# Reid_Orthotic_v2_IO.net
KiCad netlist of a schematic drawn in Altium Designer
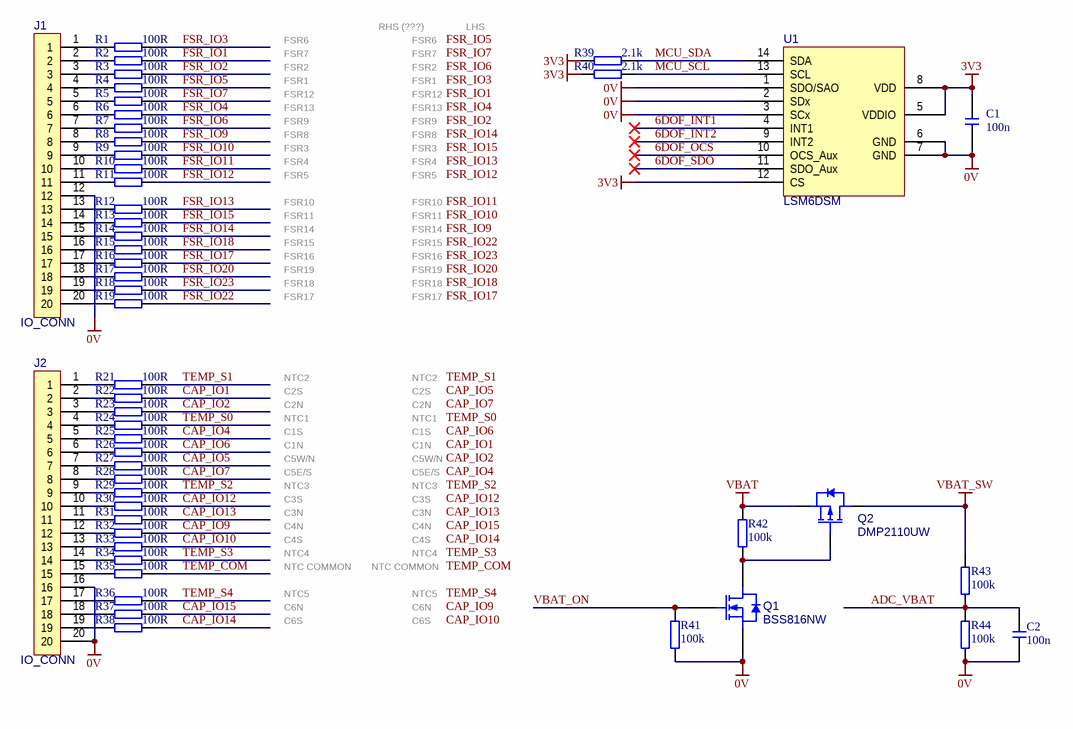
[diagram p0: Reid Orthotic v2 IO.SchDoc]

(export (version "E")
  (design (tool "Eeschema 10.0.6"))
  (components
    (comp (ref "C1")
      (value "100n")
      (footprint "0402 CAP HD")
      (libsource (lib "zoo589 PCB Library") (part "Capacitor"))
    )
    (comp (ref "C2")
      (value "100n")
      (footprint "0402 CAP HD")
      (libsource (lib "zoo589 PCB Library") (part "Capacitor"))
    )
    (comp (ref "J1")
      (value "IO_CONN")
      (footprint "IO_CONN")
      (libsource (lib "Reid Orthotic v2") (part "IO_CONN"))
    )
    (comp (ref "J2")
      (value "IO_CONN")
      (footprint "IO_CONN")
      (libsource (lib "Reid Orthotic v2") (part "IO_CONN"))
    )
    (comp (ref "Q1")
      (value "BSS816NW")
      (footprint "SOT323")
      (libsource (lib "Earthoffset Prototype v1 PCB Library") (part "MOSFET N-CH"))
    )
    (comp (ref "Q2")
      (value "DMP2110UW")
      (footprint "SOT323")
      (libsource (lib "zoo589 PCB Library") (part "MOSFET PCH"))
    )
    (comp (ref "R1")
      (value "100R")
      (footprint "0402 RES HD")
      (libsource (lib "zoo589 PCB Library") (part "Resistor"))
    )
    (comp (ref "R2")
      (value "100R")
      (footprint "0402 RES HD")
      (libsource (lib "zoo589 PCB Library") (part "Resistor"))
    )
    (comp (ref "R3")
      (value "100R")
      (footprint "0402 RES HD")
      (libsource (lib "zoo589 PCB Library") (part "Resistor"))
    )
    (comp (ref "R4")
      (value "100R")
      (footprint "0402 RES HD")
      (libsource (lib "zoo589 PCB Library") (part "Resistor"))
    )
    (comp (ref "R5")
      (value "100R")
      (footprint "0402 RES HD")
      (libsource (lib "zoo589 PCB Library") (part "Resistor"))
    )
    (comp (ref "R6")
      (value "100R")
      (footprint "0402 RES HD")
      (libsource (lib "zoo589 PCB Library") (part "Resistor"))
    )
    (comp (ref "R7")
      (value "100R")
      (footprint "0402 RES HD")
      (libsource (lib "zoo589 PCB Library") (part "Resistor"))
    )
    (comp (ref "R8")
      (value "100R")
      (footprint "0402 RES HD")
      (libsource (lib "zoo589 PCB Library") (part "Resistor"))
    )
    (comp (ref "R9")
      (value "100R")
      (footprint "0402 RES HD")
      (libsource (lib "zoo589 PCB Library") (part "Resistor"))
    )
    (comp (ref "R10")
      (value "100R")
      (footprint "0402 RES HD")
      (libsource (lib "zoo589 PCB Library") (part "Resistor"))
    )
    (comp (ref "R11")
      (value "100R")
      (footprint "0402 RES HD")
      (libsource (lib "zoo589 PCB Library") (part "Resistor"))
    )
    (comp (ref "R12")
      (value "100R")
      (footprint "0402 RES HD")
      (libsource (lib "zoo589 PCB Library") (part "Resistor"))
    )
    (comp (ref "R13")
      (value "100R")
      (footprint "0402 RES HD")
      (libsource (lib "zoo589 PCB Library") (part "Resistor"))
    )
    (comp (ref "R14")
      (value "100R")
      (footprint "0402 RES HD")
      (libsource (lib "zoo589 PCB Library") (part "Resistor"))
    )
    (comp (ref "R15")
      (value "100R")
      (footprint "0402 RES HD")
      (libsource (lib "zoo589 PCB Library") (part "Resistor"))
    )
    (comp (ref "R16")
      (value "100R")
      (footprint "0402 RES HD")
      (libsource (lib "zoo589 PCB Library") (part "Resistor"))
    )
    (comp (ref "R17")
      (value "100R")
      (footprint "0402 RES HD")
      (libsource (lib "zoo589 PCB Library") (part "Resistor"))
    )
    (comp (ref "R18")
      (value "100R")
      (footprint "0402 RES HD")
      (libsource (lib "zoo589 PCB Library") (part "Resistor"))
    )
    (comp (ref "R19")
      (value "100R")
      (footprint "0402 RES HD")
      (libsource (lib "zoo589 PCB Library") (part "Resistor"))
    )
    (comp (ref "R21")
      (value "100R")
      (footprint "0402 RES HD")
      (libsource (lib "zoo589 PCB Library") (part "Resistor"))
    )
    (comp (ref "R22")
      (value "100R")
      (footprint "0402 RES HD")
      (libsource (lib "zoo589 PCB Library") (part "Resistor"))
    )
    (comp (ref "R23")
      (value "100R")
      (footprint "0402 RES HD")
      (libsource (lib "zoo589 PCB Library") (part "Resistor"))
    )
    (comp (ref "R24")
      (value "100R")
      (footprint "0402 RES HD")
      (libsource (lib "zoo589 PCB Library") (part "Resistor"))
    )
    (comp (ref "R25")
      (value "100R")
      (footprint "0402 RES HD")
      (libsource (lib "zoo589 PCB Library") (part "Resistor"))
    )
    (comp (ref "R26")
      (value "100R")
      (footprint "0402 RES HD")
      (libsource (lib "zoo589 PCB Library") (part "Resistor"))
    )
    (comp (ref "R27")
      (value "100R")
      (footprint "0402 RES HD")
      (libsource (lib "zoo589 PCB Library") (part "Resistor"))
    )
    (comp (ref "R28")
      (value "100R")
      (footprint "0402 RES HD")
      (libsource (lib "zoo589 PCB Library") (part "Resistor"))
    )
    (comp (ref "R29")
      (value "100R")
      (footprint "0402 RES HD")
      (libsource (lib "zoo589 PCB Library") (part "Resistor"))
    )
    (comp (ref "R30")
      (value "100R")
      (footprint "0402 RES HD")
      (libsource (lib "zoo589 PCB Library") (part "Resistor"))
    )
    (comp (ref "R31")
      (value "100R")
      (footprint "0402 RES HD")
      (libsource (lib "zoo589 PCB Library") (part "Resistor"))
    )
    (comp (ref "R32")
      (value "100R")
      (footprint "0402 RES HD")
      (libsource (lib "zoo589 PCB Library") (part "Resistor"))
    )
    (comp (ref "R33")
      (value "100R")
      (footprint "0402 RES HD")
      (libsource (lib "zoo589 PCB Library") (part "Resistor"))
    )
    (comp (ref "R34")
      (value "100R")
      (footprint "0402 RES HD")
      (libsource (lib "zoo589 PCB Library") (part "Resistor"))
    )
    (comp (ref "R35")
      (value "100R")
      (footprint "0402 RES HD")
      (libsource (lib "zoo589 PCB Library") (part "Resistor"))
    )
    (comp (ref "R36")
      (value "100R")
      (footprint "0402 RES HD")
      (libsource (lib "zoo589 PCB Library") (part "Resistor"))
    )
    (comp (ref "R37")
      (value "100R")
      (footprint "0402 RES HD")
      (libsource (lib "zoo589 PCB Library") (part "Resistor"))
    )
    (comp (ref "R38")
      (value "100R")
      (footprint "0402 RES HD")
      (libsource (lib "zoo589 PCB Library") (part "Resistor"))
    )
    (comp (ref "R39")
      (value "2.1k")
      (footprint "0402 RES HD")
      (libsource (lib "zoo589 PCB Library") (part "Resistor"))
    )
    (comp (ref "R40")
      (value "2.1k")
      (footprint "0402 RES HD")
      (libsource (lib "zoo589 PCB Library") (part "Resistor"))
    )
    (comp (ref "R41")
      (value "100k")
      (footprint "0402 RES HD")
      (libsource (lib "zoo589 PCB Library") (part "Resistor"))
    )
    (comp (ref "R42")
      (value "100k")
      (footprint "0402 RES HD")
      (libsource (lib "zoo589 PCB Library") (part "Resistor"))
    )
    (comp (ref "R43")
      (value "100k")
      (footprint "0402 RES HD")
      (libsource (lib "zoo589 PCB Library") (part "Resistor"))
    )
    (comp (ref "R44")
      (value "100k")
      (footprint "0402 RES HD")
      (libsource (lib "zoo589 PCB Library") (part "Resistor"))
    )
    (comp (ref "U1")
      (value "LSM6DSM")
      (footprint "LSM6DSM")
      (libsource (lib "CarbonCircuits Part Library") (part "LSM6DSM"))
    )
  )
  (nets
    (net (code "1") (name "/6DOF_INT1") (class "Default")
      (node (ref "U1") (pin "4") (pinfunction "INT1_4") (pintype "passive+no_connect"))
    )
    (net (code "2") (name "/6DOF_INT2") (class "Default")
      (node (ref "U1") (pin "9") (pinfunction "INT2_9") (pintype "passive+no_connect"))
    )
    (net (code "3") (name "/6DOF_OCS") (class "Default")
      (node (ref "U1") (pin "10") (pinfunction "OCS_Aux_10") (pintype "passive+no_connect"))
    )
    (net (code "4") (name "/6DOF_SDO") (class "Default")
      (node (ref "U1") (pin "11") (pinfunction "SDO_Aux_11") (pintype "passive+no_connect"))
    )
    (net (code "5") (name "/ADC_VBAT") (class "Default")
      (node (ref "C2") (pin "1") (pinfunction "1_1") (pintype "passive"))
      (node (ref "R43") (pin "2") (pinfunction "2_2") (pintype "passive"))
      (node (ref "R44") (pin "1") (pinfunction "1_1") (pintype "passive"))
    )
    (net (code "6") (name "/CAP_IO1") (class "Default")
      (node (ref "R22") (pin "1") (pinfunction "1_1") (pintype "passive"))
    )
    (net (code "7") (name "/CAP_IO2") (class "Default")
      (node (ref "R23") (pin "1") (pinfunction "1_1") (pintype "passive"))
    )
    (net (code "8") (name "/CAP_IO4") (class "Default")
      (node (ref "R25") (pin "1") (pinfunction "1_1") (pintype "passive"))
    )
    (net (code "9") (name "/CAP_IO5") (class "Default")
      (node (ref "R27") (pin "1") (pinfunction "1_1") (pintype "passive"))
    )
    (net (code "10") (name "/CAP_IO6") (class "Default")
      (node (ref "R26") (pin "1") (pinfunction "1_1") (pintype "passive"))
    )
    (net (code "11") (name "/CAP_IO7") (class "Default")
      (node (ref "R28") (pin "1") (pinfunction "1_1") (pintype "passive"))
    )
    (net (code "12") (name "/CAP_IO9") (class "Default")
      (node (ref "R32") (pin "1") (pinfunction "1_1") (pintype "passive"))
    )
    (net (code "13") (name "/CAP_IO10") (class "Default")
      (node (ref "R33") (pin "1") (pinfunction "1_1") (pintype "passive"))
    )
    (net (code "14") (name "/CAP_IO12") (class "Default")
      (node (ref "R30") (pin "1") (pinfunction "1_1") (pintype "passive"))
    )
    (net (code "15") (name "/CAP_IO13") (class "Default")
      (node (ref "R31") (pin "1") (pinfunction "1_1") (pintype "passive"))
    )
    (net (code "16") (name "/CAP_IO14") (class "Default")
      (node (ref "R38") (pin "1") (pinfunction "1_1") (pintype "passive"))
    )
    (net (code "17") (name "/CAP_IO15") (class "Default")
      (node (ref "R37") (pin "1") (pinfunction "1_1") (pintype "passive"))
    )
    (net (code "18") (name "/FSR_IO1") (class "Default")
      (node (ref "R2") (pin "1") (pinfunction "1_1") (pintype "passive"))
    )
    (net (code "19") (name "/FSR_IO2") (class "Default")
      (node (ref "R3") (pin "1") (pinfunction "1_1") (pintype "passive"))
    )
    (net (code "20") (name "/FSR_IO3") (class "Default")
      (node (ref "R1") (pin "1") (pinfunction "1_1") (pintype "passive"))
    )
    (net (code "21") (name "/FSR_IO4") (class "Default")
      (node (ref "R6") (pin "1") (pinfunction "1_1") (pintype "passive"))
    )
    (net (code "22") (name "/FSR_IO5") (class "Default")
      (node (ref "R4") (pin "1") (pinfunction "1_1") (pintype "passive"))
    )
    (net (code "23") (name "/FSR_IO6") (class "Default")
      (node (ref "R7") (pin "1") (pinfunction "1_1") (pintype "passive"))
    )
    (net (code "24") (name "/FSR_IO7") (class "Default")
      (node (ref "R5") (pin "1") (pinfunction "1_1") (pintype "passive"))
    )
    (net (code "25") (name "/FSR_IO9") (class "Default")
      (node (ref "R8") (pin "1") (pinfunction "1_1") (pintype "passive"))
    )
    (net (code "26") (name "/FSR_IO10") (class "Default")
      (node (ref "R9") (pin "1") (pinfunction "1_1") (pintype "passive"))
    )
    (net (code "27") (name "/FSR_IO11") (class "Default")
      (node (ref "R10") (pin "1") (pinfunction "1_1") (pintype "passive"))
    )
    (net (code "28") (name "/FSR_IO12") (class "Default")
      (node (ref "R11") (pin "1") (pinfunction "1_1") (pintype "passive"))
    )
    (net (code "29") (name "/FSR_IO13") (class "Default")
      (node (ref "R12") (pin "1") (pinfunction "1_1") (pintype "passive"))
    )
    (net (code "30") (name "/FSR_IO14") (class "Default")
      (node (ref "R14") (pin "1") (pinfunction "1_1") (pintype "passive"))
    )
    (net (code "31") (name "/FSR_IO15") (class "Default")
      (node (ref "R13") (pin "1") (pinfunction "1_1") (pintype "passive"))
    )
    (net (code "32") (name "/FSR_IO17") (class "Default")
      (node (ref "R16") (pin "1") (pinfunction "1_1") (pintype "passive"))
    )
    (net (code "33") (name "/FSR_IO18") (class "Default")
      (node (ref "R15") (pin "1") (pinfunction "1_1") (pintype "passive"))
    )
    (net (code "34") (name "/FSR_IO20") (class "Default")
      (node (ref "R17") (pin "1") (pinfunction "1_1") (pintype "passive"))
    )
    (net (code "35") (name "/FSR_IO22") (class "Default")
      (node (ref "R19") (pin "1") (pinfunction "1_1") (pintype "passive"))
    )
    (net (code "36") (name "/FSR_IO23") (class "Default")
      (node (ref "R18") (pin "1") (pinfunction "1_1") (pintype "passive"))
    )
    (net (code "37") (name "/MCU_SCL") (class "Default")
      (node (ref "R40") (pin "1") (pinfunction "1_1") (pintype "passive"))
      (node (ref "U1") (pin "13") (pinfunction "SCL_13") (pintype "passive"))
    )
    (net (code "38") (name "/MCU_SDA") (class "Default")
      (node (ref "R39") (pin "1") (pinfunction "1_1") (pintype "passive"))
      (node (ref "U1") (pin "14") (pinfunction "SDA_14") (pintype "passive"))
    )
    (net (code "39") (name "/TEMP_COM") (class "Default")
      (node (ref "R35") (pin "1") (pinfunction "1_1") (pintype "passive"))
    )
    (net (code "40") (name "/TEMP_S0") (class "Default")
      (node (ref "R24") (pin "1") (pinfunction "1_1") (pintype "passive"))
    )
    (net (code "41") (name "/TEMP_S1") (class "Default")
      (node (ref "R21") (pin "1") (pinfunction "1_1") (pintype "passive"))
    )
    (net (code "42") (name "/TEMP_S2") (class "Default")
      (node (ref "R29") (pin "1") (pinfunction "1_1") (pintype "passive"))
    )
    (net (code "43") (name "/TEMP_S3") (class "Default")
      (node (ref "R34") (pin "1") (pinfunction "1_1") (pintype "passive"))
    )
    (net (code "44") (name "/TEMP_S4") (class "Default")
      (node (ref "R36") (pin "1") (pinfunction "1_1") (pintype "passive"))
    )
    (net (code "45") (name "/VBAT_ON") (class "Default")
      (node (ref "Q1") (pin "1") (pinfunction "G_1") (pintype "passive"))
      (node (ref "R41") (pin "1") (pinfunction "1_1") (pintype "passive"))
    )
    (net (code "46") (name "0V") (class "Default")
      (node (ref "C1") (pin "1") (pinfunction "1_1") (pintype "passive"))
      (node (ref "C2") (pin "2") (pinfunction "2_2") (pintype "passive"))
      (node (ref "J1") (pin "12") (pinfunction "12_12") (pintype "passive"))
      (node (ref "J2") (pin "16") (pinfunction "16_16") (pintype "passive"))
      (node (ref "J2") (pin "20") (pinfunction "20_20") (pintype "passive"))
      (node (ref "Q1") (pin "2") (pinfunction "S_2") (pintype "passive"))
      (node (ref "R41") (pin "2") (pinfunction "2_2") (pintype "passive"))
      (node (ref "R44") (pin "2") (pinfunction "2_2") (pintype "passive"))
      (node (ref "U1") (pin "1") (pinfunction "SDO/SAO_1") (pintype "passive"))
      (node (ref "U1") (pin "2") (pinfunction "SDx_2") (pintype "passive"))
      (node (ref "U1") (pin "3") (pinfunction "SCx_3") (pintype "passive"))
      (node (ref "U1") (pin "6") (pinfunction "GND_6") (pintype "passive"))
      (node (ref "U1") (pin "7") (pinfunction "GND_7") (pintype "passive"))
    )
    (net (code "47") (name "3V3") (class "Default")
      (node (ref "C1") (pin "2") (pinfunction "2_2") (pintype "passive"))
      (node (ref "R39") (pin "2") (pinfunction "2_2") (pintype "passive"))
      (node (ref "R40") (pin "2") (pinfunction "2_2") (pintype "passive"))
      (node (ref "U1") (pin "12") (pinfunction "CS_12") (pintype "passive"))
      (node (ref "U1") (pin "5") (pinfunction "VDDIO_5") (pintype "passive"))
      (node (ref "U1") (pin "8") (pinfunction "VDD_8") (pintype "passive"))
    )
    (net (code "48") (name "Net-(J1-Pad1)") (class "Default")
      (node (ref "J1") (pin "1") (pinfunction "1_1") (pintype "passive"))
      (node (ref "R1") (pin "2") (pinfunction "2_2") (pintype "passive"))
    )
    (net (code "49") (name "Net-(J1-Pad2)") (class "Default")
      (node (ref "J1") (pin "2") (pinfunction "2_2") (pintype "passive"))
      (node (ref "R2") (pin "2") (pinfunction "2_2") (pintype "passive"))
    )
    (net (code "50") (name "Net-(J1-Pad3)") (class "Default")
      (node (ref "J1") (pin "3") (pinfunction "3_3") (pintype "passive"))
      (node (ref "R3") (pin "2") (pinfunction "2_2") (pintype "passive"))
    )
    (net (code "51") (name "Net-(J1-Pad4)") (class "Default")
      (node (ref "J1") (pin "4") (pinfunction "4_4") (pintype "passive"))
      (node (ref "R4") (pin "2") (pinfunction "2_2") (pintype "passive"))
    )
    (net (code "52") (name "Net-(J1-Pad5)") (class "Default")
      (node (ref "J1") (pin "5") (pinfunction "5_5") (pintype "passive"))
      (node (ref "R5") (pin "2") (pinfunction "2_2") (pintype "passive"))
    )
    (net (code "53") (name "Net-(J1-Pad6)") (class "Default")
      (node (ref "J1") (pin "6") (pinfunction "6_6") (pintype "passive"))
      (node (ref "R6") (pin "2") (pinfunction "2_2") (pintype "passive"))
    )
    (net (code "54") (name "Net-(J1-Pad7)") (class "Default")
      (node (ref "J1") (pin "7") (pinfunction "7_7") (pintype "passive"))
      (node (ref "R7") (pin "2") (pinfunction "2_2") (pintype "passive"))
    )
    (net (code "55") (name "Net-(J1-Pad8)") (class "Default")
      (node (ref "J1") (pin "8") (pinfunction "8_8") (pintype "passive"))
      (node (ref "R8") (pin "2") (pinfunction "2_2") (pintype "passive"))
    )
    (net (code "56") (name "Net-(J1-Pad9)") (class "Default")
      (node (ref "J1") (pin "9") (pinfunction "9_9") (pintype "passive"))
      (node (ref "R9") (pin "2") (pinfunction "2_2") (pintype "passive"))
    )
    (net (code "57") (name "Net-(J1-Pad10)") (class "Default")
      (node (ref "J1") (pin "10") (pinfunction "10_10") (pintype "passive"))
      (node (ref "R10") (pin "2") (pinfunction "2_2") (pintype "passive"))
    )
    (net (code "58") (name "Net-(J1-Pad11)") (class "Default")
      (node (ref "J1") (pin "11") (pinfunction "11_11") (pintype "passive"))
      (node (ref "R11") (pin "2") (pinfunction "2_2") (pintype "passive"))
    )
    (net (code "59") (name "Net-(J1-Pad13)") (class "Default")
      (node (ref "J1") (pin "13") (pinfunction "13_13") (pintype "passive"))
      (node (ref "R12") (pin "2") (pinfunction "2_2") (pintype "passive"))
    )
    (net (code "60") (name "Net-(J1-Pad14)") (class "Default")
      (node (ref "J1") (pin "14") (pinfunction "14_14") (pintype "passive"))
      (node (ref "R13") (pin "2") (pinfunction "2_2") (pintype "passive"))
    )
    (net (code "61") (name "Net-(J1-Pad15)") (class "Default")
      (node (ref "J1") (pin "15") (pinfunction "15_15") (pintype "passive"))
      (node (ref "R14") (pin "2") (pinfunction "2_2") (pintype "passive"))
    )
    (net (code "62") (name "Net-(J1-Pad16)") (class "Default")
      (node (ref "J1") (pin "16") (pinfunction "16_16") (pintype "passive"))
      (node (ref "R15") (pin "2") (pinfunction "2_2") (pintype "passive"))
    )
    (net (code "63") (name "Net-(J1-Pad17)") (class "Default")
      (node (ref "J1") (pin "17") (pinfunction "17_17") (pintype "passive"))
      (node (ref "R16") (pin "2") (pinfunction "2_2") (pintype "passive"))
    )
    (net (code "64") (name "Net-(J1-Pad18)") (class "Default")
      (node (ref "J1") (pin "18") (pinfunction "18_18") (pintype "passive"))
      (node (ref "R17") (pin "2") (pinfunction "2_2") (pintype "passive"))
    )
    (net (code "65") (name "Net-(J1-Pad19)") (class "Default")
      (node (ref "J1") (pin "19") (pinfunction "19_19") (pintype "passive"))
      (node (ref "R18") (pin "2") (pinfunction "2_2") (pintype "passive"))
    )
    (net (code "66") (name "Net-(J1-Pad20)") (class "Default")
      (node (ref "J1") (pin "20") (pinfunction "20_20") (pintype "passive"))
      (node (ref "R19") (pin "2") (pinfunction "2_2") (pintype "passive"))
    )
    (net (code "67") (name "Net-(J2-Pad1)") (class "Default")
      (node (ref "J2") (pin "1") (pinfunction "1_1") (pintype "passive"))
      (node (ref "R21") (pin "2") (pinfunction "2_2") (pintype "passive"))
    )
    (net (code "68") (name "Net-(J2-Pad2)") (class "Default")
      (node (ref "J2") (pin "2") (pinfunction "2_2") (pintype "passive"))
      (node (ref "R22") (pin "2") (pinfunction "2_2") (pintype "passive"))
    )
    (net (code "69") (name "Net-(J2-Pad3)") (class "Default")
      (node (ref "J2") (pin "3") (pinfunction "3_3") (pintype "passive"))
      (node (ref "R23") (pin "2") (pinfunction "2_2") (pintype "passive"))
    )
    (net (code "70") (name "Net-(J2-Pad4)") (class "Default")
      (node (ref "J2") (pin "4") (pinfunction "4_4") (pintype "passive"))
      (node (ref "R24") (pin "2") (pinfunction "2_2") (pintype "passive"))
    )
    (net (code "71") (name "Net-(J2-Pad5)") (class "Default")
      (node (ref "J2") (pin "5") (pinfunction "5_5") (pintype "passive"))
      (node (ref "R25") (pin "2") (pinfunction "2_2") (pintype "passive"))
    )
    (net (code "72") (name "Net-(J2-Pad6)") (class "Default")
      (node (ref "J2") (pin "6") (pinfunction "6_6") (pintype "passive"))
      (node (ref "R26") (pin "2") (pinfunction "2_2") (pintype "passive"))
    )
    (net (code "73") (name "Net-(J2-Pad7)") (class "Default")
      (node (ref "J2") (pin "7") (pinfunction "7_7") (pintype "passive"))
      (node (ref "R27") (pin "2") (pinfunction "2_2") (pintype "passive"))
    )
    (net (code "74") (name "Net-(J2-Pad8)") (class "Default")
      (node (ref "J2") (pin "8") (pinfunction "8_8") (pintype "passive"))
      (node (ref "R28") (pin "2") (pinfunction "2_2") (pintype "passive"))
    )
    (net (code "75") (name "Net-(J2-Pad9)") (class "Default")
      (node (ref "J2") (pin "9") (pinfunction "9_9") (pintype "passive"))
      (node (ref "R29") (pin "2") (pinfunction "2_2") (pintype "passive"))
    )
    (net (code "76") (name "Net-(J2-Pad10)") (class "Default")
      (node (ref "J2") (pin "10") (pinfunction "10_10") (pintype "passive"))
      (node (ref "R30") (pin "2") (pinfunction "2_2") (pintype "passive"))
    )
    (net (code "77") (name "Net-(J2-Pad11)") (class "Default")
      (node (ref "J2") (pin "11") (pinfunction "11_11") (pintype "passive"))
      (node (ref "R31") (pin "2") (pinfunction "2_2") (pintype "passive"))
    )
    (net (code "78") (name "Net-(J2-Pad12)") (class "Default")
      (node (ref "J2") (pin "12") (pinfunction "12_12") (pintype "passive"))
      (node (ref "R32") (pin "2") (pinfunction "2_2") (pintype "passive"))
    )
    (net (code "79") (name "Net-(J2-Pad13)") (class "Default")
      (node (ref "J2") (pin "13") (pinfunction "13_13") (pintype "passive"))
      (node (ref "R33") (pin "2") (pinfunction "2_2") (pintype "passive"))
    )
    (net (code "80") (name "Net-(J2-Pad14)") (class "Default")
      (node (ref "J2") (pin "14") (pinfunction "14_14") (pintype "passive"))
      (node (ref "R34") (pin "2") (pinfunction "2_2") (pintype "passive"))
    )
    (net (code "81") (name "Net-(J2-Pad15)") (class "Default")
      (node (ref "J2") (pin "15") (pinfunction "15_15") (pintype "passive"))
      (node (ref "R35") (pin "2") (pinfunction "2_2") (pintype "passive"))
    )
    (net (code "82") (name "Net-(J2-Pad17)") (class "Default")
      (node (ref "J2") (pin "17") (pinfunction "17_17") (pintype "passive"))
      (node (ref "R36") (pin "2") (pinfunction "2_2") (pintype "passive"))
    )
    (net (code "83") (name "Net-(J2-Pad18)") (class "Default")
      (node (ref "J2") (pin "18") (pinfunction "18_18") (pintype "passive"))
      (node (ref "R37") (pin "2") (pinfunction "2_2") (pintype "passive"))
    )
    (net (code "84") (name "Net-(J2-Pad19)") (class "Default")
      (node (ref "J2") (pin "19") (pinfunction "19_19") (pintype "passive"))
      (node (ref "R38") (pin "2") (pinfunction "2_2") (pintype "passive"))
    )
    (net (code "85") (name "Net-(Q1-D)") (class "Default")
      (node (ref "Q1") (pin "3") (pinfunction "D_3") (pintype "passive"))
      (node (ref "Q2") (pin "1") (pinfunction "G_1") (pintype "passive"))
      (node (ref "R42") (pin "2") (pinfunction "2_2") (pintype "passive"))
    )
    (net (code "86") (name "VBAT") (class "Default")
      (node (ref "Q2") (pin "2") (pinfunction "S_2") (pintype "passive"))
      (node (ref "R42") (pin "1") (pinfunction "1_1") (pintype "passive"))
    )
    (net (code "87") (name "VBAT_SW") (class "Default")
      (node (ref "Q2") (pin "3") (pinfunction "D_3") (pintype "passive"))
      (node (ref "R43") (pin "1") (pinfunction "1_1") (pintype "passive"))
    )
  )
)
